# M311A.net
KiCad netlist of a schematic drawn in EAGLE
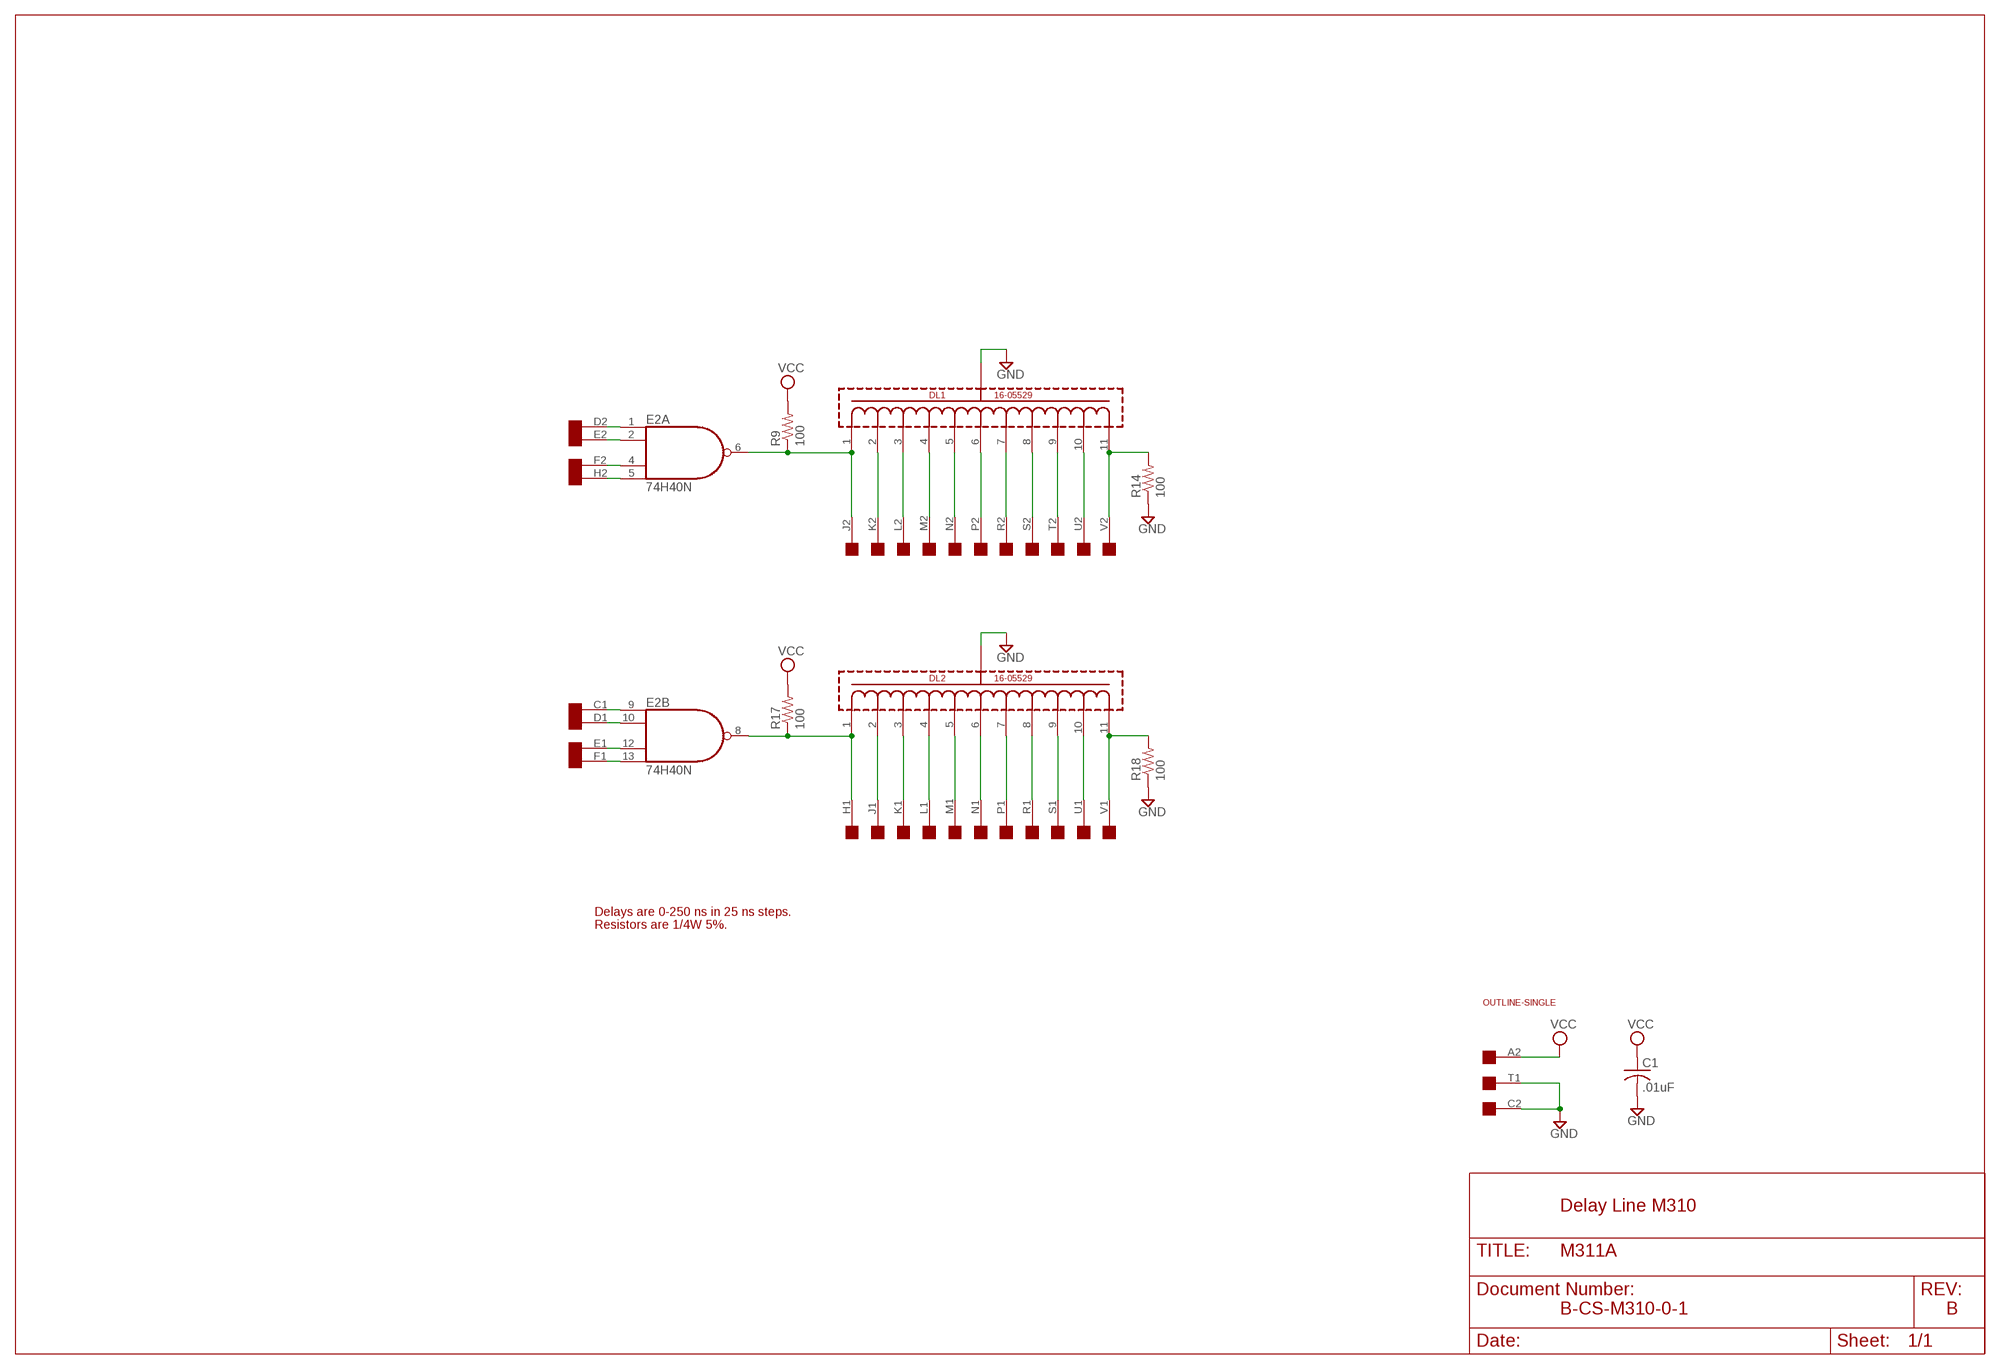
[diagram p0: schematic, sheet 1]

(export (version "E")
  (design (tool "Eeschema 10.0.6"))
  (components
    (comp (ref "C1")
      (value ".01uF")
      (footprint "eagle-import:C050-025X075")
      (libsource (lib "eagle-import") (part "C-US050-025X075"))
    )
    (comp (ref "DL1")
      (value "16-05529")
      (footprint "eagle-import:16-05529")
      (libsource (lib "eagle-import") (part "16-05529"))
    )
    (comp (ref "DL2")
      (value "16-05529")
      (footprint "eagle-import:16-05529")
      (libsource (lib "eagle-import") (part "16-05529"))
    )
    (comp (ref "E2")
      (value "74H40N")
      (footprint "eagle-import:DIL14")
      (libsource (lib "eagle-import") (part "7420NS"))
    )
    (comp (ref "R9")
      (value "100")
      (footprint "eagle-import:0207_10")
      (libsource (lib "eagle-import") (part "R-US_0207/10"))
    )
    (comp (ref "R14")
      (value "100")
      (footprint "eagle-import:0207_10")
      (libsource (lib "eagle-import") (part "R-US_0207/10"))
    )
    (comp (ref "R17")
      (value "100")
      (footprint "eagle-import:0207_10")
      (libsource (lib "eagle-import") (part "R-US_0207/10"))
    )
    (comp (ref "R18")
      (value "100")
      (footprint "eagle-import:0207_10")
      (libsource (lib "eagle-import") (part "R-US_0207/10"))
    )
    (comp (ref "U$1")
      (value "OUTLINE-SINGLE")
      (footprint "eagle-import:SINGLE")
      (libsource (lib "eagle-import") (part "OUTLINE-SINGLE"))
    )
    (comp (ref "U$4")
      (value "SINGLE")
      (footprint "eagle-import:EDGE-CON2")
      (libsource (lib "eagle-import") (part "SINGLE"))
    )
  )
  (nets
    (net (code "1") (name "GND") (class "Default")
      (node (ref "C1") (pin "2") (pinfunction "2_2") (pintype "passive"))
      (node (ref "DL1") (pin "12") (pinfunction "GND_12") (pintype "passive"))
      (node (ref "DL2") (pin "12") (pinfunction "GND_12") (pintype "passive"))
      (node (ref "R14") (pin "1") (pinfunction "1_1") (pintype "passive"))
      (node (ref "R18") (pin "1") (pinfunction "1_1") (pintype "passive"))
      (node (ref "U$4") (pin "C2") (pinfunction "1_C2") (pintype "bidirectional"))
      (node (ref "U$4") (pin "T1") (pinfunction "1_T1") (pintype "bidirectional"))
    )
    (net (code "2") (name "Net-(DL1-0)") (class "Default")
      (node (ref "DL1") (pin "1") (pinfunction "0_1") (pintype "passive"))
      (node (ref "E2") (pin "6") (pinfunction "O_6") (pintype "output"))
      (node (ref "R9") (pin "1") (pinfunction "1_1") (pintype "passive"))
      (node (ref "U$4") (pin "J2") (pinfunction "1_J2") (pintype "bidirectional"))
    )
    (net (code "3") (name "Net-(DL1-5)") (class "Default")
      (node (ref "DL1") (pin "2") (pinfunction "5_2") (pintype "passive"))
      (node (ref "U$4") (pin "K2") (pinfunction "1_K2") (pintype "bidirectional"))
    )
    (net (code "4") (name "Net-(DL1-10)") (class "Default")
      (node (ref "DL1") (pin "3") (pinfunction "10_3") (pintype "passive"))
      (node (ref "U$4") (pin "L2") (pinfunction "1_L2") (pintype "bidirectional"))
    )
    (net (code "5") (name "Net-(DL1-15)") (class "Default")
      (node (ref "DL1") (pin "4") (pinfunction "15_4") (pintype "passive"))
      (node (ref "U$4") (pin "M2") (pinfunction "1_M2") (pintype "bidirectional"))
    )
    (net (code "6") (name "Net-(DL1-20)") (class "Default")
      (node (ref "DL1") (pin "5") (pinfunction "20_5") (pintype "passive"))
      (node (ref "U$4") (pin "N2") (pinfunction "1_N2") (pintype "bidirectional"))
    )
    (net (code "7") (name "Net-(DL1-25)") (class "Default")
      (node (ref "DL1") (pin "6") (pinfunction "25_6") (pintype "passive"))
      (node (ref "U$4") (pin "P2") (pinfunction "1_P2") (pintype "bidirectional"))
    )
    (net (code "8") (name "Net-(DL1-30)") (class "Default")
      (node (ref "DL1") (pin "7") (pinfunction "30_7") (pintype "passive"))
      (node (ref "U$4") (pin "R2") (pinfunction "1_R2") (pintype "bidirectional"))
    )
    (net (code "9") (name "Net-(DL1-35)") (class "Default")
      (node (ref "DL1") (pin "8") (pinfunction "35_8") (pintype "passive"))
      (node (ref "U$4") (pin "S2") (pinfunction "1_S2") (pintype "bidirectional"))
    )
    (net (code "10") (name "Net-(DL1-40)") (class "Default")
      (node (ref "DL1") (pin "9") (pinfunction "40_9") (pintype "passive"))
      (node (ref "U$4") (pin "T2") (pinfunction "1_T2") (pintype "bidirectional"))
    )
    (net (code "11") (name "Net-(DL1-45)") (class "Default")
      (node (ref "DL1") (pin "10") (pinfunction "45_10") (pintype "passive"))
      (node (ref "U$4") (pin "U2") (pinfunction "1_U2") (pintype "bidirectional"))
    )
    (net (code "12") (name "Net-(DL1-50)") (class "Default")
      (node (ref "DL1") (pin "11") (pinfunction "50_11") (pintype "passive"))
      (node (ref "R14") (pin "2") (pinfunction "2_2") (pintype "passive"))
      (node (ref "U$4") (pin "V2") (pinfunction "1_V2") (pintype "bidirectional"))
    )
    (net (code "13") (name "Net-(DL2-0)") (class "Default")
      (node (ref "DL2") (pin "1") (pinfunction "0_1") (pintype "passive"))
      (node (ref "E2") (pin "8") (pinfunction "O_8") (pintype "output"))
      (node (ref "R17") (pin "1") (pinfunction "1_1") (pintype "passive"))
      (node (ref "U$4") (pin "H1") (pinfunction "1_H1") (pintype "bidirectional"))
    )
    (net (code "14") (name "Net-(DL2-5)") (class "Default")
      (node (ref "DL2") (pin "2") (pinfunction "5_2") (pintype "passive"))
      (node (ref "U$4") (pin "J1") (pinfunction "1_J1") (pintype "bidirectional"))
    )
    (net (code "15") (name "Net-(DL2-10)") (class "Default")
      (node (ref "DL2") (pin "3") (pinfunction "10_3") (pintype "passive"))
      (node (ref "U$4") (pin "K1") (pinfunction "1_K1") (pintype "bidirectional"))
    )
    (net (code "16") (name "Net-(DL2-15)") (class "Default")
      (node (ref "DL2") (pin "4") (pinfunction "15_4") (pintype "passive"))
      (node (ref "U$4") (pin "L1") (pinfunction "1_L1") (pintype "bidirectional"))
    )
    (net (code "17") (name "Net-(DL2-20)") (class "Default")
      (node (ref "DL2") (pin "5") (pinfunction "20_5") (pintype "passive"))
      (node (ref "U$4") (pin "M1") (pinfunction "1_M1") (pintype "bidirectional"))
    )
    (net (code "18") (name "Net-(DL2-25)") (class "Default")
      (node (ref "DL2") (pin "6") (pinfunction "25_6") (pintype "passive"))
      (node (ref "U$4") (pin "N1") (pinfunction "1_N1") (pintype "bidirectional"))
    )
    (net (code "19") (name "Net-(DL2-30)") (class "Default")
      (node (ref "DL2") (pin "7") (pinfunction "30_7") (pintype "passive"))
      (node (ref "U$4") (pin "P1") (pinfunction "1_P1") (pintype "bidirectional"))
    )
    (net (code "20") (name "Net-(DL2-35)") (class "Default")
      (node (ref "DL2") (pin "8") (pinfunction "35_8") (pintype "passive"))
      (node (ref "U$4") (pin "R1") (pinfunction "1_R1") (pintype "bidirectional"))
    )
    (net (code "21") (name "Net-(DL2-40)") (class "Default")
      (node (ref "DL2") (pin "9") (pinfunction "40_9") (pintype "passive"))
      (node (ref "U$4") (pin "S1") (pinfunction "1_S1") (pintype "bidirectional"))
    )
    (net (code "22") (name "Net-(DL2-45)") (class "Default")
      (node (ref "DL2") (pin "10") (pinfunction "45_10") (pintype "passive"))
      (node (ref "U$4") (pin "U1") (pinfunction "1_U1") (pintype "bidirectional"))
    )
    (net (code "23") (name "Net-(DL2-50)") (class "Default")
      (node (ref "DL2") (pin "11") (pinfunction "50_11") (pintype "passive"))
      (node (ref "R18") (pin "2") (pinfunction "2_2") (pintype "passive"))
      (node (ref "U$4") (pin "V1") (pinfunction "1_V1") (pintype "bidirectional"))
    )
    (net (code "24") (name "Net-(E2A-I0)") (class "Default")
      (node (ref "E2") (pin "1") (pinfunction "I0_1") (pintype "input"))
      (node (ref "U$4") (pin "D2") (pinfunction "1_D2") (pintype "bidirectional"))
    )
    (net (code "25") (name "Net-(E2A-I1)") (class "Default")
      (node (ref "E2") (pin "2") (pinfunction "I1_2") (pintype "input"))
      (node (ref "U$4") (pin "E2") (pinfunction "1_E2") (pintype "bidirectional"))
    )
    (net (code "26") (name "Net-(E2A-I2)") (class "Default")
      (node (ref "E2") (pin "4") (pinfunction "I2_4") (pintype "input"))
      (node (ref "U$4") (pin "F2") (pinfunction "1_F2") (pintype "bidirectional"))
    )
    (net (code "27") (name "Net-(E2A-I3)") (class "Default")
      (node (ref "E2") (pin "5") (pinfunction "I3_5") (pintype "input"))
      (node (ref "U$4") (pin "H2") (pinfunction "1_H2") (pintype "bidirectional"))
    )
    (net (code "28") (name "Net-(E2B-I0)") (class "Default")
      (node (ref "E2") (pin "9") (pinfunction "I0_9") (pintype "input"))
      (node (ref "U$4") (pin "C1") (pinfunction "1_C1") (pintype "bidirectional"))
    )
    (net (code "29") (name "Net-(E2B-I1)") (class "Default")
      (node (ref "E2") (pin "10") (pinfunction "I1_10") (pintype "input"))
      (node (ref "U$4") (pin "D1") (pinfunction "1_D1") (pintype "bidirectional"))
    )
    (net (code "30") (name "Net-(E2B-I2)") (class "Default")
      (node (ref "E2") (pin "12") (pinfunction "I2_12") (pintype "input"))
      (node (ref "U$4") (pin "E1") (pinfunction "1_E1") (pintype "bidirectional"))
    )
    (net (code "31") (name "Net-(E2B-I3)") (class "Default")
      (node (ref "E2") (pin "13") (pinfunction "I3_13") (pintype "input"))
      (node (ref "U$4") (pin "F1") (pinfunction "1_F1") (pintype "bidirectional"))
    )
    (net (code "32") (name "VCC") (class "Default")
      (node (ref "C1") (pin "1") (pinfunction "1_1") (pintype "passive"))
      (node (ref "R17") (pin "2") (pinfunction "2_2") (pintype "passive"))
      (node (ref "R9") (pin "2") (pinfunction "2_2") (pintype "passive"))
      (node (ref "U$4") (pin "A2") (pinfunction "1_A2") (pintype "bidirectional"))
    )
  )
)
